# openSX70_ALPHA_V6-2-2-20181103.net
KiCad netlist of a schematic drawn in EAGLE
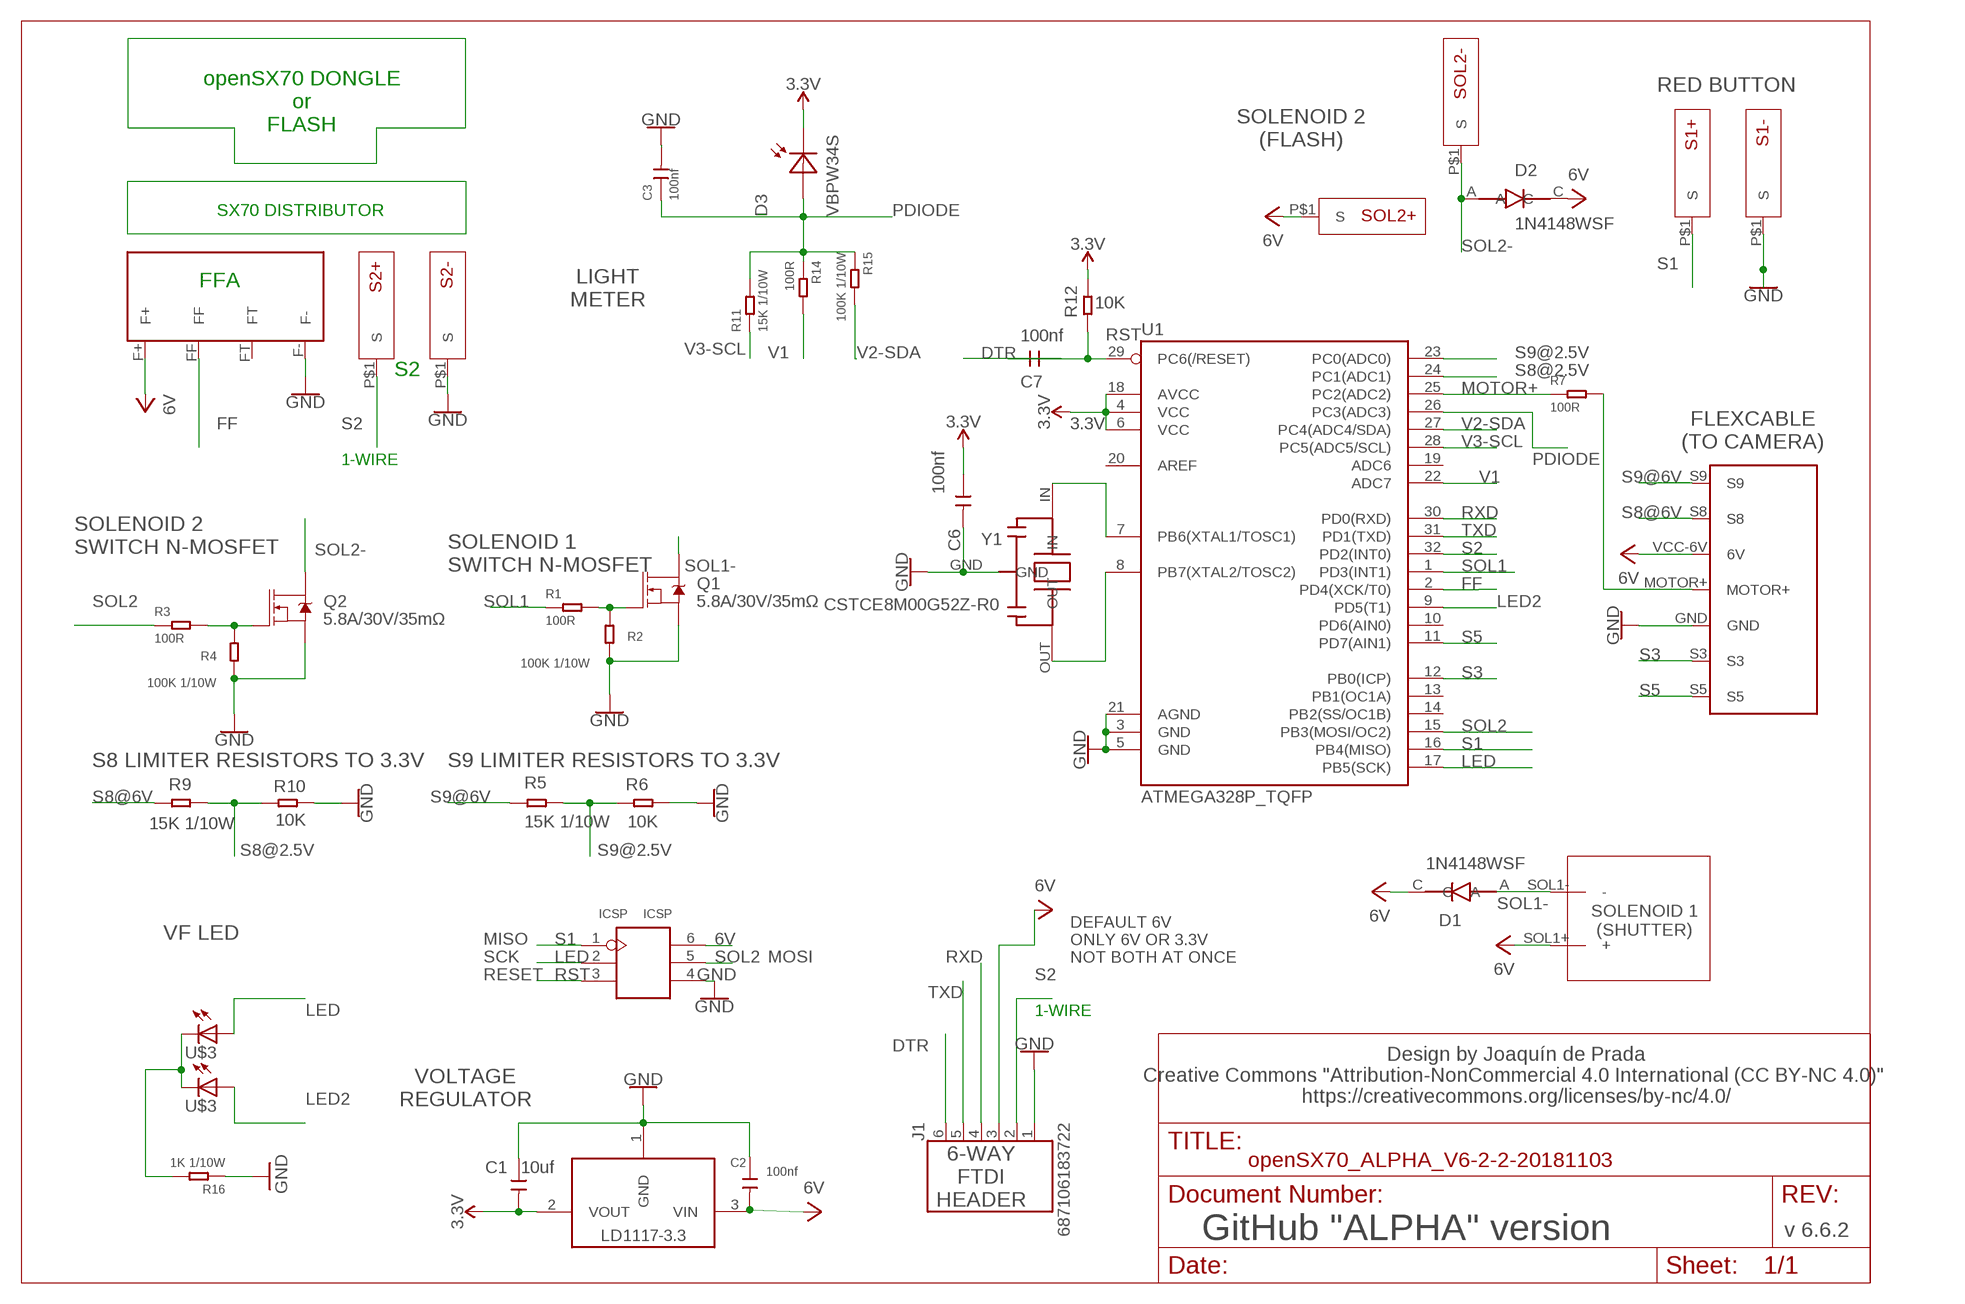
[diagram p0: schematic, sheet 1]

(export (version "E")
  (design (tool "Eeschema 10.0.6"))
  (components
    (comp (ref "C1")
      (value "10uf")
      (footprint "eagle-import:C0603")
      (fields (field (name "MPN") "CC0603KRX5R6BB106"))
      (libsource (lib "eagle-import") (part "CERAMIC-10UF-10V-10%-X5R(0603)"))
    )
    (comp (ref "C2")
      (value "100nf")
      (footprint "eagle-import:C0603")
      (fields (field (name "MPN") "CC0603KRX7R9BB104"))
      (libsource (lib "eagle-import") (part "CERAMIC-100NF-50V-10%-X7R(0603)"))
    )
    (comp (ref "C3")
      (value "100nf")
      (footprint "eagle-import:C0603")
      (fields (field (name "MPN") "CC0603KRX7R9BB104"))
      (libsource (lib "eagle-import") (part "CERAMIC-100NF-50V-10%-X7R(0603)"))
    )
    (comp (ref "C6")
      (value "100nf")
      (footprint "eagle-import:C0603")
      (fields (field (name "MPN") "CC0603KRX7R9BB104"))
      (libsource (lib "eagle-import") (part "CERAMIC-100NF-50V-10%-X7R(0603)"))
    )
    (comp (ref "C7")
      (value "100nf")
      (footprint "eagle-import:C0603")
      (fields (field (name "MPN") "CC0603KRX7R9BB104"))
      (libsource (lib "eagle-import") (part "CERAMIC-100NF-50V-10%-X7R(0603)"))
    )
    (comp (ref "D1")
      (value "1N4148WSF")
      (footprint "eagle-import:SODFL2512X100N")
      (fields (field (name "MANUFACTURER") "Fairchild Semiconductor"))
      (libsource (lib "eagle-import") (part "1N4148WS"))
    )
    (comp (ref "D2")
      (value "1N4148WSF")
      (footprint "eagle-import:SODFL2512X100N")
      (fields (field (name "MANUFACTURER") "Fairchild Semiconductor"))
      (libsource (lib "eagle-import") (part "1N4148WS"))
    )
    (comp (ref "D3")
      (value "VBPW34S")
      (footprint "eagle-import:SOD6439X130N")
      (fields (field (name "DIGI-KEY_PART_NUMBER") "751-1500-1-ND") (field (name "MF") "Vishay"))
      (libsource (lib "eagle-import") (part "VBPW34S"))
    )
    (comp (ref "ICSP")
      (value "ICSP")
      (footprint "eagle-import:H2X3-2.54")
      (libsource (lib "eagle-import") (part "ICSP"))
    )
    (comp (ref "J1")
      (value "687106183722")
      (footprint "eagle-import:687106183722")
      (fields (field (name "MF") "Wurth Electronics"))
      (libsource (lib "eagle-import") (part "687106183722"))
    )
    (comp (ref "LD11172.5V")
      (value "LD1117 2.5V")
      (footprint "eagle-import:SOT223")
      (fields (field (name "MF") "Advanced Monolithic Systems") (field (name "MP") "AMS1117-5.0"))
      (libsource (lib "eagle-import") (part "LD1117-3.3"))
    )
    (comp (ref "Q1")
      (value "5.8A/30V/35mΩ")
      (footprint "eagle-import:SOT23-3")
      (libsource (lib "eagle-import") (part "MOSFET-NCH-AO3404A"))
    )
    (comp (ref "Q2")
      (value "5.8A/30V/35mΩ")
      (footprint "eagle-import:SOT23-3")
      (libsource (lib "eagle-import") (part "MOSFET-NCH-AO3404A"))
    )
    (comp (ref "R1")
      (value "100R")
      (footprint "eagle-import:R0603")
      (fields (field (name "MPN") "RC0603JR-07100RL"))
      (libsource (lib "eagle-import") (part "SMD-RES-100R-5%-1/10W(0603)"))
    )
    (comp (ref "R2")
      (value "100K 1/10W")
      (footprint "eagle-import:R0603")
      (fields (field (name "MPN") "RC0603JR-07100KL"))
      (libsource (lib "eagle-import") (part "SMD-RES-100K-5%-1/10W(0603)"))
    )
    (comp (ref "R3")
      (value "100R")
      (footprint "eagle-import:R0603")
      (fields (field (name "MPN") "RC0603JR-07100RL"))
      (libsource (lib "eagle-import") (part "SMD-RES-100R-5%-1/10W(0603)"))
    )
    (comp (ref "R4")
      (value "100K 1/10W")
      (footprint "eagle-import:R0603")
      (fields (field (name "MPN") "RC0603JR-07100KL"))
      (libsource (lib "eagle-import") (part "SMD-RES-100K-5%-1/10W(0603)"))
    )
    (comp (ref "R5")
      (value "15K 1/10W")
      (footprint "eagle-import:R0603")
      (fields (field (name "MPN") "RC0603FR-0715KL"))
      (libsource (lib "eagle-import") (part "SMD-RES-15K-1%-1/10W(0603)"))
    )
    (comp (ref "R6")
      (value "10K")
      (footprint "eagle-import:R0603")
      (fields (field (name "MPN") "RC0603FR-0710KL"))
      (libsource (lib "eagle-import") (part "SMD-RES-10K-1%-1/10W(0603)"))
    )
    (comp (ref "R7")
      (value "100R")
      (footprint "eagle-import:R0603")
      (fields (field (name "MPN") "RC0603JR-07100RL"))
      (libsource (lib "eagle-import") (part "SMD-RES-100R-5%-1/10W(0603)"))
    )
    (comp (ref "R9")
      (value "15K 1/10W")
      (footprint "eagle-import:R0603")
      (fields (field (name "MPN") "RC0603FR-0715KL"))
      (libsource (lib "eagle-import") (part "SMD-RES-15K-1%-1/10W(0603)"))
    )
    (comp (ref "R10")
      (value "10K")
      (footprint "eagle-import:R0603")
      (fields (field (name "MPN") "RC0603FR-0710KL"))
      (libsource (lib "eagle-import") (part "SMD-RES-10K-1%-1/10W(0603)"))
    )
    (comp (ref "R11")
      (value "15K 1/10W")
      (footprint "eagle-import:R0603")
      (fields (field (name "MPN") "RC0603FR-0715KL"))
      (libsource (lib "eagle-import") (part "SMD-RES-15K-1%-1/10W(0603)"))
    )
    (comp (ref "R12")
      (value "10K")
      (footprint "eagle-import:R0603")
      (fields (field (name "MPN") "RC0603FR-0710KL"))
      (libsource (lib "eagle-import") (part "SMD-RES-10K-1%-1/10W(0603)"))
    )
    (comp (ref "R14")
      (value "100R")
      (footprint "eagle-import:R0603")
      (fields (field (name "MPN") "RC0603JR-07100RL"))
      (libsource (lib "eagle-import") (part "SMD-RES-100R-5%-1/10W(0603)"))
    )
    (comp (ref "R15")
      (value "100K 1/10W")
      (footprint "eagle-import:R0603")
      (fields (field (name "MPN") "RC0603JR-07100KL"))
      (libsource (lib "eagle-import") (part "SMD-RES-100K-5%-1/10W(0603)"))
    )
    (comp (ref "R16")
      (value "1K 1/10W")
      (footprint "eagle-import:R0603")
      (fields (field (name "MPN") "RC0603JR-071KL"))
      (libsource (lib "eagle-import") (part "SMD-RES-1K-5%-1/10W(0603)"))
    )
    (comp (ref "S1+")
      (value "SX70-S-PAD-NEW")
      (footprint "eagle-import:SX70-S-PAD2")
      (libsource (lib "eagle-import") (part "SX70-S-PAD-NEW"))
    )
    (comp (ref "S1-")
      (value "SX70-S-PAD-NEW")
      (footprint "eagle-import:SX70-S-PAD2")
      (libsource (lib "eagle-import") (part "SX70-S-PAD-NEW"))
    )
    (comp (ref "S2+")
      (value "SX70-S-PAD-NEW")
      (footprint "eagle-import:SX70-S-PAD2")
      (libsource (lib "eagle-import") (part "SX70-S-PAD-NEW"))
    )
    (comp (ref "S2-")
      (value "SX70-S-PAD-NEW")
      (footprint "eagle-import:SX70-S-PAD2")
      (libsource (lib "eagle-import") (part "SX70-S-PAD-NEW"))
    )
    (comp (ref "SOL1")
      (value "SX70-SOLENOID1-2PADS")
      (footprint "eagle-import:SX70-SOLENOID1-2")
      (libsource (lib "eagle-import") (part "SX70-SOLENOID1-2PADS"))
    )
    (comp (ref "SOL2+")
      (value "SX70-S-PAD-NEW")
      (footprint "eagle-import:SX70-S-PAD2")
      (libsource (lib "eagle-import") (part "SX70-S-PAD-NEW"))
    )
    (comp (ref "SOL2-")
      (value "SX70-S-PAD-NEW")
      (footprint "eagle-import:SX70-S-PAD2")
      (libsource (lib "eagle-import") (part "SX70-S-PAD-NEW"))
    )
    (comp (ref "U$1")
      (value "SX70-7-PAD")
      (footprint "eagle-import:SX70-7-PAD")
      (libsource (lib "eagle-import") (part "SX70-7-PAD"))
    )
    (comp (ref "U$2")
      (value "FFA")
      (footprint "eagle-import:FFA-PAD-PACKAGE")
      (libsource (lib "eagle-import") (part "SX70-FFA-PAD"))
    )
    (comp (ref "U$3")
      (value "DUAL-LED-0603-BIS")
      (footprint "eagle-import:LED_APHB1608SYKSURKC")
      (libsource (lib "eagle-import") (part "DUAL-LED-0603-BIS"))
    )
    (comp (ref "U1")
      (value "ATMEGA328P_TQFP")
      (footprint "eagle-import:TQFP32-08")
      (libsource (lib "eagle-import") (part "ATMEGA328P_TQFP"))
    )
    (comp (ref "Y1")
      (value "CSTCE8M00G52Z-R0")
      (footprint "eagle-import:CFP95P160X100-3N")
      (fields (field (name "MF") "Murata") (field (name "MP") "CSTCE16M0V53-R0"))
      (libsource (lib "eagle-import") (part "CSTCE16M0V53-R0"))
    )
  )
  (nets
    (net (code "1") (name "/DTR") (class "Default")
      (node (ref "C7") (pin "1") (pinfunction "1_1") (pintype "passive"))
      (node (ref "J1") (pin "6") (pinfunction "1_6") (pintype "passive"))
    )
    (net (code "2") (name "/FF") (class "Default")
      (node (ref "U$2") (pin "FF") (pinfunction "FF_FF") (pintype "bidirectional"))
      (node (ref "U1") (pin "2") (pinfunction "PD4(XCK/T0)_2") (pintype "bidirectional"))
    )
    (net (code "3") (name "/LED") (class "Default")
      (node (ref "ICSP") (pin "2") (pinfunction "SCK_2") (pintype "bidirectional"))
      (node (ref "U$3") (pin "1") (pinfunction "A_1") (pintype "passive"))
      (node (ref "U1") (pin "17") (pinfunction "PB5(SCK)_17") (pintype "bidirectional"))
    )
    (net (code "4") (name "/LED2") (class "Default")
      (node (ref "U$3") (pin "3") (pinfunction "A1_3") (pintype "passive"))
      (node (ref "U1") (pin "9") (pinfunction "PD5(T1)_9") (pintype "bidirectional"))
    )
    (net (code "5") (name "/MOTOR+") (class "Default")
      (node (ref "R7") (pin "1") (pinfunction "1_1") (pintype "passive"))
      (node (ref "U1") (pin "25") (pinfunction "PC2(ADC2)_25") (pintype "bidirectional"))
    )
    (net (code "6") (name "/PDIODE") (class "Default")
      (node (ref "C3") (pin "1") (pinfunction "1_1") (pintype "passive"))
      (node (ref "D3") (pin "A") (pinfunction "A_A") (pintype "passive"))
      (node (ref "R11") (pin "2") (pinfunction "2_2") (pintype "passive"))
      (node (ref "R14") (pin "1") (pinfunction "1_1") (pintype "passive"))
      (node (ref "R15") (pin "1") (pinfunction "1_1") (pintype "passive"))
      (node (ref "U1") (pin "26") (pinfunction "PC3(ADC3)_26") (pintype "bidirectional"))
    )
    (net (code "7") (name "/RST") (class "Default")
      (node (ref "C7") (pin "2") (pinfunction "2_2") (pintype "passive"))
      (node (ref "ICSP") (pin "3") (pinfunction "RST_3") (pintype "bidirectional"))
      (node (ref "R12") (pin "1") (pinfunction "1_1") (pintype "passive"))
      (node (ref "U1") (pin "29") (pinfunction "PC6(/RESET)_29") (pintype "bidirectional"))
    )
    (net (code "8") (name "/RXD") (class "Default")
      (node (ref "J1") (pin "4") (pinfunction "3_4") (pintype "passive"))
      (node (ref "U1") (pin "30") (pinfunction "PD0(RXD)_30") (pintype "bidirectional"))
    )
    (net (code "9") (name "/S1") (class "Default")
      (node (ref "ICSP") (pin "1") (pinfunction "MISO_1") (pintype "bidirectional"))
      (node (ref "S1+") (pin "P$1") (pinfunction "S_P$1") (pintype "bidirectional"))
      (node (ref "U1") (pin "16") (pinfunction "PB4(MISO)_16") (pintype "bidirectional"))
    )
    (net (code "10") (name "/S2") (class "Default")
      (node (ref "J1") (pin "2") (pinfunction "5_2") (pintype "passive"))
      (node (ref "S2+") (pin "P$1") (pinfunction "S_P$1") (pintype "bidirectional"))
      (node (ref "U1") (pin "32") (pinfunction "PD2(INT0)_32") (pintype "bidirectional"))
    )
    (net (code "11") (name "/S3") (class "Default")
      (node (ref "U$1") (pin "S3") (pinfunction "S3_S3") (pintype "bidirectional"))
      (node (ref "U1") (pin "12") (pinfunction "PB0(ICP)_12") (pintype "bidirectional"))
    )
    (net (code "12") (name "/S5") (class "Default")
      (node (ref "U$1") (pin "S5") (pinfunction "S5_S5") (pintype "bidirectional"))
      (node (ref "U1") (pin "11") (pinfunction "PD7(AIN1)_11") (pintype "bidirectional"))
    )
    (net (code "13") (name "/S8@2.5V") (class "Default")
      (node (ref "R10") (pin "1") (pinfunction "1_1") (pintype "passive"))
      (node (ref "R9") (pin "2") (pinfunction "2_2") (pintype "passive"))
      (node (ref "U1") (pin "24") (pinfunction "PC1(ADC1)_24") (pintype "bidirectional"))
    )
    (net (code "14") (name "/S8@6V") (class "Default")
      (node (ref "R9") (pin "1") (pinfunction "1_1") (pintype "passive"))
      (node (ref "U$1") (pin "S8") (pinfunction "S8_S8") (pintype "bidirectional"))
    )
    (net (code "15") (name "/S9@2.5V") (class "Default")
      (node (ref "R5") (pin "2") (pinfunction "2_2") (pintype "passive"))
      (node (ref "R6") (pin "1") (pinfunction "1_1") (pintype "passive"))
      (node (ref "U1") (pin "23") (pinfunction "PC0(ADC0)_23") (pintype "bidirectional"))
    )
    (net (code "16") (name "/S9@6V") (class "Default")
      (node (ref "R5") (pin "1") (pinfunction "1_1") (pintype "passive"))
      (node (ref "U$1") (pin "S9") (pinfunction "S9_S9") (pintype "bidirectional"))
    )
    (net (code "17") (name "/SOL1") (class "Default")
      (node (ref "R1") (pin "1") (pinfunction "1_1") (pintype "passive"))
      (node (ref "U1") (pin "1") (pinfunction "PD3(INT1)_1") (pintype "bidirectional"))
    )
    (net (code "18") (name "/SOL1-") (class "Default")
      (node (ref "D1") (pin "A") (pinfunction "A_A") (pintype "passive"))
      (node (ref "Q1") (pin "3") (pinfunction "D_3") (pintype "bidirectional"))
      (node (ref "SOL1") (pin "SOL1-") (pinfunction "-_SOL1-") (pintype "bidirectional"))
    )
    (net (code "19") (name "/SOL2") (class "Default")
      (node (ref "ICSP") (pin "5") (pinfunction "MOSI_5") (pintype "bidirectional"))
      (node (ref "R3") (pin "1") (pinfunction "1_1") (pintype "passive"))
      (node (ref "U1") (pin "15") (pinfunction "PB3(MOSI/OC2)_15") (pintype "bidirectional"))
    )
    (net (code "20") (name "/SOL2-") (class "Default")
      (node (ref "D2") (pin "A") (pinfunction "A_A") (pintype "passive"))
      (node (ref "Q2") (pin "3") (pinfunction "D_3") (pintype "bidirectional"))
      (node (ref "SOL2-") (pin "P$1") (pinfunction "S_P$1") (pintype "bidirectional"))
    )
    (net (code "21") (name "/TXD") (class "Default")
      (node (ref "J1") (pin "5") (pinfunction "2_5") (pintype "passive"))
      (node (ref "U1") (pin "31") (pinfunction "PD1(TXD)_31") (pintype "bidirectional"))
    )
    (net (code "22") (name "/V1") (class "Default")
      (node (ref "R14") (pin "2") (pinfunction "2_2") (pintype "passive"))
      (node (ref "U1") (pin "22") (pinfunction "ADC7_22") (pintype "bidirectional"))
    )
    (net (code "23") (name "/V2-SDA") (class "Default")
      (node (ref "R15") (pin "2") (pinfunction "2_2") (pintype "passive"))
      (node (ref "U1") (pin "27") (pinfunction "PC4(ADC4/SDA)_27") (pintype "bidirectional"))
    )
    (net (code "24") (name "/V3-SCL") (class "Default")
      (node (ref "R11") (pin "1") (pinfunction "1_1") (pintype "passive"))
      (node (ref "U1") (pin "28") (pinfunction "PC5(ADC5/SCL)_28") (pintype "bidirectional"))
    )
    (net (code "25") (name "3.3V") (class "Default")
      (node (ref "C1") (pin "2") (pinfunction "2_2") (pintype "passive"))
      (node (ref "C6") (pin "1") (pinfunction "1_1") (pintype "passive"))
      (node (ref "D3") (pin "C") (pinfunction "C_C") (pintype "passive"))
      (node (ref "LD11172.5V") (pin "2") (pinfunction "VOUT_2") (pintype "bidirectional"))
      (node (ref "R12") (pin "2") (pinfunction "2_2") (pintype "passive"))
      (node (ref "U1") (pin "18") (pinfunction "AVCC_18") (pintype "bidirectional"))
      (node (ref "U1") (pin "4") (pinfunction "VCC_4") (pintype "bidirectional"))
      (node (ref "U1") (pin "6") (pinfunction "VCC_6") (pintype "bidirectional"))
    )
    (net (code "26") (name "6V") (class "Default")
      (node (ref "C2") (pin "2") (pinfunction "2_2") (pintype "passive"))
      (node (ref "D1") (pin "C") (pinfunction "C_C") (pintype "passive"))
      (node (ref "D2") (pin "C") (pinfunction "C_C") (pintype "passive"))
      (node (ref "ICSP") (pin "6") (pinfunction "VCC_6") (pintype "bidirectional"))
      (node (ref "J1") (pin "3") (pinfunction "4_3") (pintype "passive"))
      (node (ref "LD11172.5V") (pin "3") (pinfunction "VIN_3") (pintype "bidirectional"))
      (node (ref "SOL1") (pin "SOL1+") (pinfunction "+_SOL1+") (pintype "bidirectional"))
      (node (ref "SOL2+") (pin "P$1") (pinfunction "S_P$1") (pintype "bidirectional"))
      (node (ref "U$1") (pin "VCC-6V") (pinfunction "6V_VCC-6V") (pintype "bidirectional"))
      (node (ref "U$2") (pin "F+") (pinfunction "F+_F+") (pintype "bidirectional"))
    )
    (net (code "27") (name "GND") (class "Default")
      (node (ref "C1") (pin "1") (pinfunction "1_1") (pintype "passive"))
      (node (ref "C2") (pin "1") (pinfunction "1_1") (pintype "passive"))
      (node (ref "C3") (pin "2") (pinfunction "2_2") (pintype "passive"))
      (node (ref "C6") (pin "2") (pinfunction "2_2") (pintype "passive"))
      (node (ref "ICSP") (pin "4") (pinfunction "GND_4") (pintype "bidirectional"))
      (node (ref "J1") (pin "1") (pinfunction "6_1") (pintype "passive"))
      (node (ref "LD11172.5V") (pin "1") (pinfunction "GND_1") (pintype "bidirectional"))
      (node (ref "Q1") (pin "2") (pinfunction "S_2") (pintype "bidirectional"))
      (node (ref "Q2") (pin "2") (pinfunction "S_2") (pintype "bidirectional"))
      (node (ref "R10") (pin "2") (pinfunction "2_2") (pintype "passive"))
      (node (ref "R16") (pin "1") (pinfunction "1_1") (pintype "passive"))
      (node (ref "R2") (pin "1") (pinfunction "1_1") (pintype "passive"))
      (node (ref "R4") (pin "1") (pinfunction "1_1") (pintype "passive"))
      (node (ref "R6") (pin "2") (pinfunction "2_2") (pintype "passive"))
      (node (ref "S1-") (pin "P$1") (pinfunction "S_P$1") (pintype "bidirectional"))
      (node (ref "S2-") (pin "P$1") (pinfunction "S_P$1") (pintype "bidirectional"))
      (node (ref "U$1") (pin "GND") (pinfunction "GND_GND") (pintype "bidirectional"))
      (node (ref "U$2") (pin "F-") (pinfunction "F-_F-") (pintype "bidirectional"))
      (node (ref "U1") (pin "21") (pinfunction "AGND_21") (pintype "bidirectional"))
      (node (ref "U1") (pin "3") (pinfunction "GND_3") (pintype "bidirectional"))
      (node (ref "U1") (pin "5") (pinfunction "GND_5") (pintype "bidirectional"))
      (node (ref "Y1") (pin "GND") (pinfunction "GND_GND") (pintype "passive"))
    )
    (net (code "28") (name "Net-(Q1-G)") (class "Default")
      (node (ref "Q1") (pin "1") (pinfunction "G_1") (pintype "bidirectional"))
      (node (ref "R1") (pin "2") (pinfunction "2_2") (pintype "passive"))
      (node (ref "R2") (pin "2") (pinfunction "2_2") (pintype "passive"))
    )
    (net (code "29") (name "Net-(Q2-G)") (class "Default")
      (node (ref "Q2") (pin "1") (pinfunction "G_1") (pintype "bidirectional"))
      (node (ref "R3") (pin "2") (pinfunction "2_2") (pintype "passive"))
      (node (ref "R4") (pin "2") (pinfunction "2_2") (pintype "passive"))
    )
    (net (code "30") (name "Net-(R7-Pad2)") (class "Default")
      (node (ref "R7") (pin "2") (pinfunction "2_2") (pintype "passive"))
      (node (ref "U$1") (pin "MOTOR+") (pinfunction "MOTOR+_MOTOR+") (pintype "bidirectional"))
    )
    (net (code "31") (name "Net-(U$3-C)") (class "Default")
      (node (ref "R16") (pin "2") (pinfunction "2_2") (pintype "passive"))
      (node (ref "U$3") (pin "2") (pinfunction "C_2") (pintype "passive"))
      (node (ref "U$3") (pin "4") (pinfunction "C1_4") (pintype "passive"))
    )
    (net (code "32") (name "Net-(U1-PB6(XTAL1{slash}TOSC1))") (class "Default")
      (node (ref "U1") (pin "7") (pinfunction "PB6(XTAL1/TOSC1)_7") (pintype "bidirectional"))
      (node (ref "Y1") (pin "IN") (pinfunction "IN_IN") (pintype "input"))
    )
    (net (code "33") (name "Net-(U1-PB7(XTAL2{slash}TOSC2))") (class "Default")
      (node (ref "U1") (pin "8") (pinfunction "PB7(XTAL2/TOSC2)_8") (pintype "bidirectional"))
      (node (ref "Y1") (pin "OUT") (pinfunction "OUT_OUT") (pintype "output"))
    )
    (net (code "34") (name "unconnected-(U$2-PadFT)") (class "Default")
      (node (ref "U$2") (pin "FT") (pinfunction "FT_FT") (pintype "bidirectional"))
    )
    (net (code "35") (name "unconnected-(U1-ADC6-Pad19)") (class "Default")
      (node (ref "U1") (pin "19") (pinfunction "ADC6_19") (pintype "bidirectional"))
    )
    (net (code "36") (name "unconnected-(U1-AREF-Pad20)") (class "Default")
      (node (ref "U1") (pin "20") (pinfunction "AREF_20") (pintype "bidirectional"))
    )
    (net (code "37") (name "unconnected-(U1-PB1(OC1A)-Pad13)") (class "Default")
      (node (ref "U1") (pin "13") (pinfunction "PB1(OC1A)_13") (pintype "bidirectional"))
    )
    (net (code "38") (name "unconnected-(U1-PB2(SS{slash}OC1B)-Pad14)") (class "Default")
      (node (ref "U1") (pin "14") (pinfunction "PB2(SS/OC1B)_14") (pintype "bidirectional"))
    )
    (net (code "39") (name "unconnected-(U1-PD6(AIN0)-Pad10)") (class "Default")
      (node (ref "U1") (pin "10") (pinfunction "PD6(AIN0)_10") (pintype "bidirectional"))
    )
  )
)
